# nixie_board.net
KiCad netlist of a schematic drawn in EAGLE
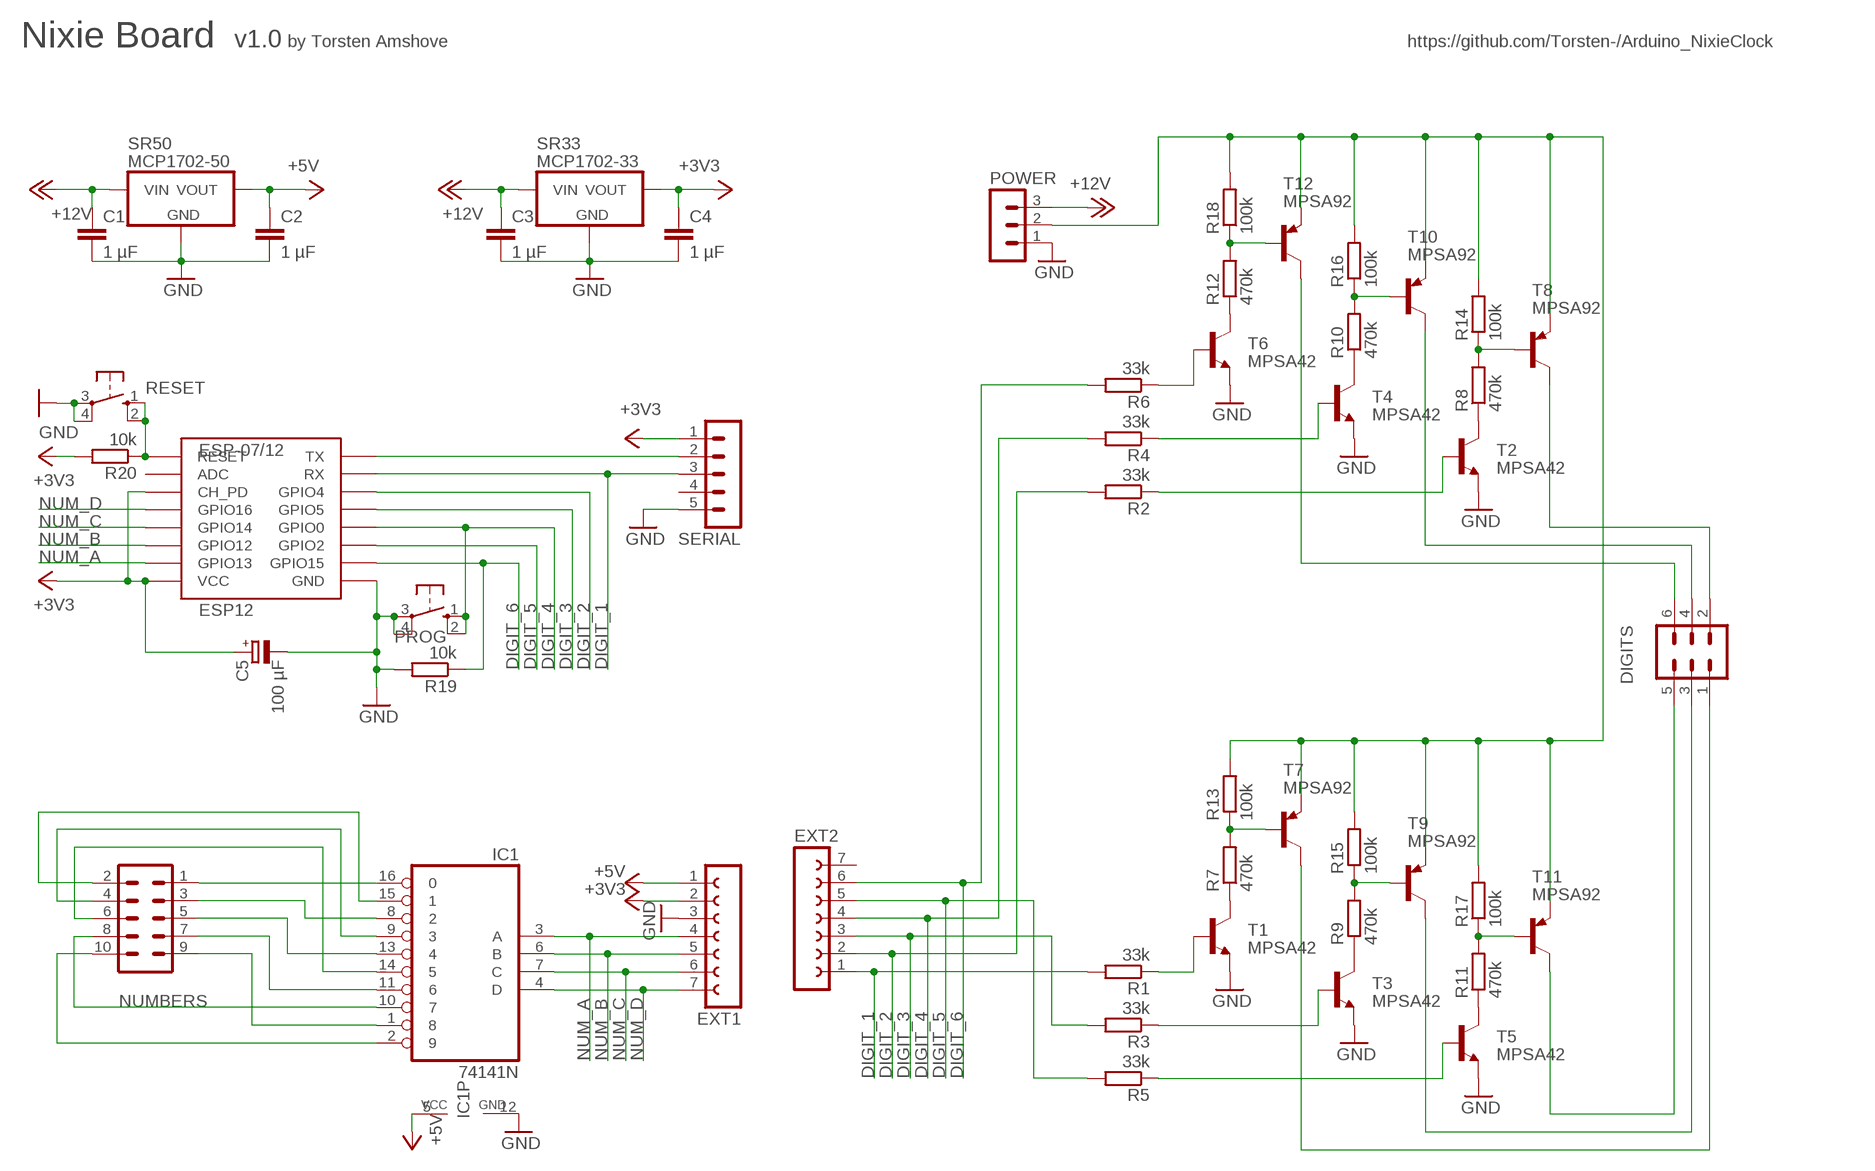
[diagram p0: schematic, sheet 1]

(export (version "E")
  (design (tool "Eeschema 10.0.6"))
  (components
    (comp (ref "C1")
      (value "1 µF")
      (footprint "eagle-import:C5B4.5")
      (libsource (lib "eagle-import") (part "C5/4.5"))
    )
    (comp (ref "C2")
      (value "1 µF")
      (footprint "eagle-import:C5B4.5")
      (libsource (lib "eagle-import") (part "C5/4.5"))
    )
    (comp (ref "C3")
      (value "1 µF")
      (footprint "eagle-import:C5B4.5")
      (libsource (lib "eagle-import") (part "C5/4.5"))
    )
    (comp (ref "C4")
      (value "1 µF")
      (footprint "eagle-import:C5B4.5")
      (libsource (lib "eagle-import") (part "C5/4.5"))
    )
    (comp (ref "C5")
      (value "100 µF")
      (footprint "eagle-import:E2,5-6")
      (libsource (lib "eagle-import") (part "CPOL-EUE2.5-6"))
    )
    (comp (ref "DIGITS")
      (value "MA03-2")
      (footprint "eagle-import:MA03-2")
      (libsource (lib "eagle-import") (part "MA03-2"))
    )
    (comp (ref "ESP-07/12")
      (value "ESP12")
      (footprint "eagle-import:ESP12")
      (libsource (lib "eagle-import") (part "ESP12"))
    )
    (comp (ref "EXT1")
      (value "FE07-1")
      (footprint "eagle-import:FE07")
      (libsource (lib "eagle-import") (part "FE07-1"))
    )
    (comp (ref "EXT2")
      (value "FE07-1")
      (footprint "eagle-import:FE07")
      (libsource (lib "eagle-import") (part "FE07-1"))
    )
    (comp (ref "IC1")
      (value "74141N")
      (footprint "eagle-import:DIL16")
      (libsource (lib "eagle-import") (part "74141N"))
    )
    (comp (ref "NUMBERS")
      (value "MA05-2")
      (footprint "eagle-import:MA05-2")
      (libsource (lib "eagle-import") (part "MA05-2"))
    )
    (comp (ref "POWER")
      (value "MA03-1")
      (footprint "eagle-import:MA03-1")
      (libsource (lib "eagle-import") (part "MA03-1"))
    )
    (comp (ref "PROG")
      (value "10-XX")
      (footprint "eagle-import:B3F-10XX")
      (fields (field (name "MPN") "B3F-1000"))
      (libsource (lib "eagle-import") (part "10-XX"))
    )
    (comp (ref "R1")
      (value "33k")
      (footprint "eagle-import:0204_7")
      (libsource (lib "eagle-import") (part "R-EU_0204/7"))
    )
    (comp (ref "R2")
      (value "33k")
      (footprint "eagle-import:0204_7")
      (libsource (lib "eagle-import") (part "R-EU_0204/7"))
    )
    (comp (ref "R3")
      (value "33k")
      (footprint "eagle-import:0204_7")
      (libsource (lib "eagle-import") (part "R-EU_0204/7"))
    )
    (comp (ref "R4")
      (value "33k")
      (footprint "eagle-import:0204_7")
      (libsource (lib "eagle-import") (part "R-EU_0204/7"))
    )
    (comp (ref "R5")
      (value "33k")
      (footprint "eagle-import:0204_7")
      (libsource (lib "eagle-import") (part "R-EU_0204/7"))
    )
    (comp (ref "R6")
      (value "33k")
      (footprint "eagle-import:0204_7")
      (libsource (lib "eagle-import") (part "R-EU_0204/7"))
    )
    (comp (ref "R7")
      (value "470k")
      (footprint "eagle-import:0204_7")
      (libsource (lib "eagle-import") (part "R-EU_0204/7"))
    )
    (comp (ref "R8")
      (value "470k")
      (footprint "eagle-import:0204_7")
      (libsource (lib "eagle-import") (part "R-EU_0204/7"))
    )
    (comp (ref "R9")
      (value "470k")
      (footprint "eagle-import:0204_7")
      (libsource (lib "eagle-import") (part "R-EU_0204/7"))
    )
    (comp (ref "R10")
      (value "470k")
      (footprint "eagle-import:0204_7")
      (libsource (lib "eagle-import") (part "R-EU_0204/7"))
    )
    (comp (ref "R11")
      (value "470k")
      (footprint "eagle-import:0204_7")
      (libsource (lib "eagle-import") (part "R-EU_0204/7"))
    )
    (comp (ref "R12")
      (value "470k")
      (footprint "eagle-import:0204_7")
      (libsource (lib "eagle-import") (part "R-EU_0204/7"))
    )
    (comp (ref "R13")
      (value "100k")
      (footprint "eagle-import:0207_2V")
      (libsource (lib "eagle-import") (part "R-EU_0207/2V"))
    )
    (comp (ref "R14")
      (value "100k")
      (footprint "eagle-import:0207_2V")
      (libsource (lib "eagle-import") (part "R-EU_0207/2V"))
    )
    (comp (ref "R15")
      (value "100k")
      (footprint "eagle-import:0207_2V")
      (libsource (lib "eagle-import") (part "R-EU_0207/2V"))
    )
    (comp (ref "R16")
      (value "100k")
      (footprint "eagle-import:0207_2V")
      (libsource (lib "eagle-import") (part "R-EU_0207/2V"))
    )
    (comp (ref "R17")
      (value "100k")
      (footprint "eagle-import:0207_2V")
      (libsource (lib "eagle-import") (part "R-EU_0207/2V"))
    )
    (comp (ref "R18")
      (value "100k")
      (footprint "eagle-import:0207_2V")
      (libsource (lib "eagle-import") (part "R-EU_0207/2V"))
    )
    (comp (ref "R19")
      (value "10k")
      (footprint "eagle-import:0204_7")
      (libsource (lib "eagle-import") (part "R-EU_0204/7"))
    )
    (comp (ref "R20")
      (value "10k")
      (footprint "eagle-import:0204_7")
      (libsource (lib "eagle-import") (part "R-EU_0204/7"))
    )
    (comp (ref "RESET")
      (value "10-XX")
      (footprint "eagle-import:B3F-10XX")
      (fields (field (name "MPN") "B3F-1000"))
      (libsource (lib "eagle-import") (part "10-XX"))
    )
    (comp (ref "SERIAL")
      (value "MA05-1")
      (footprint "eagle-import:MA05-1")
      (libsource (lib "eagle-import") (part "MA05-1"))
    )
    (comp (ref "SR33")
      (value "MCP1702-33")
      (footprint "eagle-import:TO-92")
      (libsource (lib "eagle-import") (part "MCP1702"))
    )
    (comp (ref "SR50")
      (value "MCP1702-50")
      (footprint "eagle-import:TO-92")
      (libsource (lib "eagle-import") (part "MCP1702"))
    )
    (comp (ref "T1")
      (value "MPSA42")
      (footprint "eagle-import:TO92-EBC")
      (libsource (lib "eagle-import") (part "-NPN-TO92-EBCMPSA42"))
    )
    (comp (ref "T2")
      (value "MPSA42")
      (footprint "eagle-import:TO92-EBC")
      (libsource (lib "eagle-import") (part "-NPN-TO92-EBCMPSA42"))
    )
    (comp (ref "T3")
      (value "MPSA42")
      (footprint "eagle-import:TO92-EBC")
      (libsource (lib "eagle-import") (part "-NPN-TO92-EBCMPSA42"))
    )
    (comp (ref "T4")
      (value "MPSA42")
      (footprint "eagle-import:TO92-EBC")
      (libsource (lib "eagle-import") (part "-NPN-TO92-EBCMPSA42"))
    )
    (comp (ref "T5")
      (value "MPSA42")
      (footprint "eagle-import:TO92-EBC")
      (libsource (lib "eagle-import") (part "-NPN-TO92-EBCMPSA42"))
    )
    (comp (ref "T6")
      (value "MPSA42")
      (footprint "eagle-import:TO92-EBC")
      (libsource (lib "eagle-import") (part "-NPN-TO92-EBCMPSA42"))
    )
    (comp (ref "T7")
      (value "MPSA92")
      (footprint "eagle-import:TO92-EBC")
      (libsource (lib "eagle-import") (part "-PNP-TO92-EBCMPSA92"))
    )
    (comp (ref "T8")
      (value "MPSA92")
      (footprint "eagle-import:TO92-EBC")
      (libsource (lib "eagle-import") (part "-PNP-TO92-EBCMPSA92"))
    )
    (comp (ref "T9")
      (value "MPSA92")
      (footprint "eagle-import:TO92-EBC")
      (libsource (lib "eagle-import") (part "-PNP-TO92-EBCMPSA92"))
    )
    (comp (ref "T10")
      (value "MPSA92")
      (footprint "eagle-import:TO92-EBC")
      (libsource (lib "eagle-import") (part "-PNP-TO92-EBCMPSA92"))
    )
    (comp (ref "T11")
      (value "MPSA92")
      (footprint "eagle-import:TO92-EBC")
      (libsource (lib "eagle-import") (part "-PNP-TO92-EBCMPSA92"))
    )
    (comp (ref "T12")
      (value "MPSA92")
      (footprint "eagle-import:TO92-EBC")
      (libsource (lib "eagle-import") (part "-PNP-TO92-EBCMPSA92"))
    )
  )
  (nets
    (net (code "1") (name "+3V3") (class "Default")
      (node (ref "C4") (pin "1") (pinfunction "1_1") (pintype "passive"))
      (node (ref "C5") (pin "+") (pinfunction "+_+") (pintype "passive"))
      (node (ref "ESP-07/12") (pin "CH_PD") (pinfunction "CH_PD_CH_PD") (pintype "bidirectional"))
      (node (ref "ESP-07/12") (pin "VCC") (pinfunction "VCC_VCC") (pintype "bidirectional"))
      (node (ref "EXT1") (pin "2") (pinfunction "2_2") (pintype "passive"))
      (node (ref "R20") (pin "2") (pinfunction "2_2") (pintype "passive"))
      (node (ref "SERIAL") (pin "1") (pinfunction "1_1") (pintype "passive"))
      (node (ref "SR33") (pin "3") (pinfunction "VOUT_3") (pintype "passive"))
    )
    (net (code "2") (name "+5V") (class "Default")
      (node (ref "C2") (pin "1") (pinfunction "1_1") (pintype "passive"))
      (node (ref "EXT1") (pin "1") (pinfunction "1_1") (pintype "passive"))
      (node (ref "IC1") (pin "5") (pinfunction "VCC_5") (pintype "power_in"))
      (node (ref "SR50") (pin "3") (pinfunction "VOUT_3") (pintype "passive"))
    )
    (net (code "3") (name "+12V") (class "Default")
      (node (ref "C1") (pin "1") (pinfunction "1_1") (pintype "passive"))
      (node (ref "C3") (pin "1") (pinfunction "1_1") (pintype "passive"))
      (node (ref "POWER") (pin "3") (pinfunction "3_3") (pintype "passive"))
      (node (ref "SR33") (pin "2") (pinfunction "VIN_2") (pintype "input"))
      (node (ref "SR50") (pin "2") (pinfunction "VIN_2") (pintype "input"))
    )
    (net (code "4") (name "/DIGIT_1") (class "Default")
      (node (ref "ESP-07/12") (pin "RX") (pinfunction "RX_RX") (pintype "bidirectional"))
      (node (ref "EXT2") (pin "1") (pinfunction "1_1") (pintype "passive"))
      (node (ref "R1") (pin "2") (pinfunction "2_2") (pintype "passive"))
      (node (ref "SERIAL") (pin "3") (pinfunction "3_3") (pintype "passive"))
    )
    (net (code "5") (name "/DIGIT_2") (class "Default")
      (node (ref "ESP-07/12") (pin "GPIO4") (pinfunction "GPIO4_GPIO4") (pintype "bidirectional"))
      (node (ref "EXT2") (pin "2") (pinfunction "2_2") (pintype "passive"))
      (node (ref "R2") (pin "2") (pinfunction "2_2") (pintype "passive"))
    )
    (net (code "6") (name "/DIGIT_3") (class "Default")
      (node (ref "ESP-07/12") (pin "GPIO5") (pinfunction "GPIO5_GPIO5") (pintype "bidirectional"))
      (node (ref "EXT2") (pin "3") (pinfunction "3_3") (pintype "passive"))
      (node (ref "R3") (pin "2") (pinfunction "2_2") (pintype "passive"))
    )
    (net (code "7") (name "/DIGIT_4") (class "Default")
      (node (ref "ESP-07/12") (pin "GPIO0") (pinfunction "GPIO0_GPIO0") (pintype "bidirectional"))
      (node (ref "EXT2") (pin "4") (pinfunction "4_4") (pintype "passive"))
      (node (ref "PROG") (pin "1") (pinfunction "S_1") (pintype "passive"))
      (node (ref "PROG") (pin "2") (pinfunction "S1_2") (pintype "passive"))
      (node (ref "R4") (pin "2") (pinfunction "2_2") (pintype "passive"))
    )
    (net (code "8") (name "/DIGIT_5") (class "Default")
      (node (ref "ESP-07/12") (pin "GPIO2") (pinfunction "GPIO2_GPIO2") (pintype "bidirectional"))
      (node (ref "EXT2") (pin "5") (pinfunction "5_5") (pintype "passive"))
      (node (ref "R5") (pin "2") (pinfunction "2_2") (pintype "passive"))
    )
    (net (code "9") (name "/DIGIT_6") (class "Default")
      (node (ref "ESP-07/12") (pin "GPIO15") (pinfunction "GPIO15_GPIO15") (pintype "bidirectional"))
      (node (ref "EXT2") (pin "6") (pinfunction "6_6") (pintype "passive"))
      (node (ref "R19") (pin "1") (pinfunction "1_1") (pintype "passive"))
      (node (ref "R6") (pin "2") (pinfunction "2_2") (pintype "passive"))
    )
    (net (code "10") (name "/NUM_A") (class "Default")
      (node (ref "ESP-07/12") (pin "GPIO13") (pinfunction "GPIO13_GPIO13") (pintype "bidirectional"))
      (node (ref "EXT1") (pin "4") (pinfunction "4_4") (pintype "passive"))
      (node (ref "IC1") (pin "3") (pinfunction "A_3") (pintype "input"))
    )
    (net (code "11") (name "/NUM_B") (class "Default")
      (node (ref "ESP-07/12") (pin "GPIO12") (pinfunction "GPIO12_GPIO12") (pintype "bidirectional"))
      (node (ref "EXT1") (pin "5") (pinfunction "5_5") (pintype "passive"))
      (node (ref "IC1") (pin "6") (pinfunction "B_6") (pintype "input"))
    )
    (net (code "12") (name "/NUM_C") (class "Default")
      (node (ref "ESP-07/12") (pin "GPIO14") (pinfunction "GPIO14_GPIO14") (pintype "bidirectional"))
      (node (ref "EXT1") (pin "6") (pinfunction "6_6") (pintype "passive"))
      (node (ref "IC1") (pin "7") (pinfunction "C_7") (pintype "input"))
    )
    (net (code "13") (name "/NUM_D") (class "Default")
      (node (ref "ESP-07/12") (pin "GPIO16") (pinfunction "GPIO16_GPIO16") (pintype "bidirectional"))
      (node (ref "EXT1") (pin "7") (pinfunction "7_7") (pintype "passive"))
      (node (ref "IC1") (pin "4") (pinfunction "D_4") (pintype "input"))
    )
    (net (code "14") (name "GND") (class "Default")
      (node (ref "C1") (pin "2") (pinfunction "2_2") (pintype "passive"))
      (node (ref "C2") (pin "2") (pinfunction "2_2") (pintype "passive"))
      (node (ref "C3") (pin "2") (pinfunction "2_2") (pintype "passive"))
      (node (ref "C4") (pin "2") (pinfunction "2_2") (pintype "passive"))
      (node (ref "C5") (pin "-") (pinfunction "-_-") (pintype "passive"))
      (node (ref "ESP-07/12") (pin "GND") (pinfunction "GND_GND") (pintype "bidirectional"))
      (node (ref "EXT1") (pin "3") (pinfunction "3_3") (pintype "passive"))
      (node (ref "IC1") (pin "12") (pinfunction "GND_12") (pintype "power_in"))
      (node (ref "POWER") (pin "1") (pinfunction "1_1") (pintype "passive"))
      (node (ref "PROG") (pin "3") (pinfunction "P_3") (pintype "passive"))
      (node (ref "PROG") (pin "4") (pinfunction "P1_4") (pintype "passive"))
      (node (ref "R19") (pin "2") (pinfunction "2_2") (pintype "passive"))
      (node (ref "RESET") (pin "3") (pinfunction "P_3") (pintype "passive"))
      (node (ref "RESET") (pin "4") (pinfunction "P1_4") (pintype "passive"))
      (node (ref "SERIAL") (pin "5") (pinfunction "5_5") (pintype "passive"))
      (node (ref "SR33") (pin "1") (pinfunction "GND_1") (pintype "passive"))
      (node (ref "SR50") (pin "1") (pinfunction "GND_1") (pintype "passive"))
      (node (ref "T1") (pin "E") (pinfunction "E_E") (pintype "passive"))
      (node (ref "T2") (pin "E") (pinfunction "E_E") (pintype "passive"))
      (node (ref "T3") (pin "E") (pinfunction "E_E") (pintype "passive"))
      (node (ref "T4") (pin "E") (pinfunction "E_E") (pintype "passive"))
      (node (ref "T5") (pin "E") (pinfunction "E_E") (pintype "passive"))
      (node (ref "T6") (pin "E") (pinfunction "E_E") (pintype "passive"))
    )
    (net (code "15") (name "Net-(DIGITS-Pad1)") (class "Default")
      (node (ref "DIGITS") (pin "1") (pinfunction "1_1") (pintype "passive"))
      (node (ref "T7") (pin "C") (pinfunction "C_C") (pintype "passive"))
    )
    (net (code "16") (name "Net-(DIGITS-Pad2)") (class "Default")
      (node (ref "DIGITS") (pin "2") (pinfunction "2_2") (pintype "passive"))
      (node (ref "T8") (pin "C") (pinfunction "C_C") (pintype "passive"))
    )
    (net (code "17") (name "Net-(DIGITS-Pad3)") (class "Default")
      (node (ref "DIGITS") (pin "3") (pinfunction "3_3") (pintype "passive"))
      (node (ref "T9") (pin "C") (pinfunction "C_C") (pintype "passive"))
    )
    (net (code "18") (name "Net-(DIGITS-Pad4)") (class "Default")
      (node (ref "DIGITS") (pin "4") (pinfunction "4_4") (pintype "passive"))
      (node (ref "T10") (pin "C") (pinfunction "C_C") (pintype "passive"))
    )
    (net (code "19") (name "Net-(DIGITS-Pad5)") (class "Default")
      (node (ref "DIGITS") (pin "5") (pinfunction "5_5") (pintype "passive"))
      (node (ref "T11") (pin "C") (pinfunction "C_C") (pintype "passive"))
    )
    (net (code "20") (name "Net-(DIGITS-Pad6)") (class "Default")
      (node (ref "DIGITS") (pin "6") (pinfunction "6_6") (pintype "passive"))
      (node (ref "T12") (pin "C") (pinfunction "C_C") (pintype "passive"))
    )
    (net (code "21") (name "Net-(ESP-07/12-PadTX)") (class "Default")
      (node (ref "ESP-07/12") (pin "TX") (pinfunction "TX_TX") (pintype "bidirectional"))
      (node (ref "SERIAL") (pin "2") (pinfunction "2_2") (pintype "passive"))
    )
    (net (code "22") (name "Net-(IC1A-0)") (class "Default")
      (node (ref "IC1") (pin "16") (pinfunction "0_16") (pintype "open_collector"))
      (node (ref "NUMBERS") (pin "1") (pinfunction "1_1") (pintype "passive"))
    )
    (net (code "23") (name "Net-(IC1A-1)") (class "Default")
      (node (ref "IC1") (pin "15") (pinfunction "1_15") (pintype "open_collector"))
      (node (ref "NUMBERS") (pin "2") (pinfunction "2_2") (pintype "passive"))
    )
    (net (code "24") (name "Net-(IC1A-2)") (class "Default")
      (node (ref "IC1") (pin "8") (pinfunction "2_8") (pintype "open_collector"))
      (node (ref "NUMBERS") (pin "3") (pinfunction "3_3") (pintype "passive"))
    )
    (net (code "25") (name "Net-(IC1A-3)") (class "Default")
      (node (ref "IC1") (pin "9") (pinfunction "3_9") (pintype "open_collector"))
      (node (ref "NUMBERS") (pin "4") (pinfunction "4_4") (pintype "passive"))
    )
    (net (code "26") (name "Net-(IC1A-4)") (class "Default")
      (node (ref "IC1") (pin "13") (pinfunction "4_13") (pintype "open_collector"))
      (node (ref "NUMBERS") (pin "5") (pinfunction "5_5") (pintype "passive"))
    )
    (net (code "27") (name "Net-(IC1A-5)") (class "Default")
      (node (ref "IC1") (pin "14") (pinfunction "5_14") (pintype "open_collector"))
      (node (ref "NUMBERS") (pin "6") (pinfunction "6_6") (pintype "passive"))
    )
    (net (code "28") (name "Net-(IC1A-6)") (class "Default")
      (node (ref "IC1") (pin "11") (pinfunction "6_11") (pintype "open_collector"))
      (node (ref "NUMBERS") (pin "7") (pinfunction "7_7") (pintype "passive"))
    )
    (net (code "29") (name "Net-(IC1A-7)") (class "Default")
      (node (ref "IC1") (pin "10") (pinfunction "7_10") (pintype "open_collector"))
      (node (ref "NUMBERS") (pin "8") (pinfunction "8_8") (pintype "passive"))
    )
    (net (code "30") (name "Net-(IC1A-8)") (class "Default")
      (node (ref "IC1") (pin "1") (pinfunction "8_1") (pintype "open_collector"))
      (node (ref "NUMBERS") (pin "9") (pinfunction "9_9") (pintype "passive"))
    )
    (net (code "31") (name "Net-(IC1A-9)") (class "Default")
      (node (ref "IC1") (pin "2") (pinfunction "9_2") (pintype "open_collector"))
      (node (ref "NUMBERS") (pin "10") (pinfunction "10_10") (pintype "passive"))
    )
    (net (code "32") (name "Net-(POWER-Pad2)") (class "Default")
      (node (ref "POWER") (pin "2") (pinfunction "2_2") (pintype "passive"))
      (node (ref "R13") (pin "2") (pinfunction "2_2") (pintype "passive"))
      (node (ref "R14") (pin "2") (pinfunction "2_2") (pintype "passive"))
      (node (ref "R15") (pin "2") (pinfunction "2_2") (pintype "passive"))
      (node (ref "R16") (pin "2") (pinfunction "2_2") (pintype "passive"))
      (node (ref "R17") (pin "2") (pinfunction "2_2") (pintype "passive"))
      (node (ref "R18") (pin "2") (pinfunction "2_2") (pintype "passive"))
      (node (ref "T10") (pin "E") (pinfunction "E_E") (pintype "passive"))
      (node (ref "T11") (pin "E") (pinfunction "E_E") (pintype "passive"))
      (node (ref "T12") (pin "E") (pinfunction "E_E") (pintype "passive"))
      (node (ref "T7") (pin "E") (pinfunction "E_E") (pintype "passive"))
      (node (ref "T8") (pin "E") (pinfunction "E_E") (pintype "passive"))
      (node (ref "T9") (pin "E") (pinfunction "E_E") (pintype "passive"))
    )
    (net (code "33") (name "Net-(R1-Pad1)") (class "Default")
      (node (ref "R1") (pin "1") (pinfunction "1_1") (pintype "passive"))
      (node (ref "T1") (pin "B") (pinfunction "B_B") (pintype "passive"))
    )
    (net (code "34") (name "Net-(R2-Pad1)") (class "Default")
      (node (ref "R2") (pin "1") (pinfunction "1_1") (pintype "passive"))
      (node (ref "T2") (pin "B") (pinfunction "B_B") (pintype "passive"))
    )
    (net (code "35") (name "Net-(R3-Pad1)") (class "Default")
      (node (ref "R3") (pin "1") (pinfunction "1_1") (pintype "passive"))
      (node (ref "T3") (pin "B") (pinfunction "B_B") (pintype "passive"))
    )
    (net (code "36") (name "Net-(R4-Pad1)") (class "Default")
      (node (ref "R4") (pin "1") (pinfunction "1_1") (pintype "passive"))
      (node (ref "T4") (pin "B") (pinfunction "B_B") (pintype "passive"))
    )
    (net (code "37") (name "Net-(R5-Pad1)") (class "Default")
      (node (ref "R5") (pin "1") (pinfunction "1_1") (pintype "passive"))
      (node (ref "T5") (pin "B") (pinfunction "B_B") (pintype "passive"))
    )
    (net (code "38") (name "Net-(R6-Pad1)") (class "Default")
      (node (ref "R6") (pin "1") (pinfunction "1_1") (pintype "passive"))
      (node (ref "T6") (pin "B") (pinfunction "B_B") (pintype "passive"))
    )
    (net (code "39") (name "Net-(R7-Pad1)") (class "Default")
      (node (ref "R7") (pin "1") (pinfunction "1_1") (pintype "passive"))
      (node (ref "T1") (pin "C") (pinfunction "C_C") (pintype "passive"))
    )
    (net (code "40") (name "Net-(R8-Pad1)") (class "Default")
      (node (ref "R8") (pin "1") (pinfunction "1_1") (pintype "passive"))
      (node (ref "T2") (pin "C") (pinfunction "C_C") (pintype "passive"))
    )
    (net (code "41") (name "Net-(R9-Pad1)") (class "Default")
      (node (ref "R9") (pin "1") (pinfunction "1_1") (pintype "passive"))
      (node (ref "T3") (pin "C") (pinfunction "C_C") (pintype "passive"))
    )
    (net (code "42") (name "Net-(R10-Pad1)") (class "Default")
      (node (ref "R10") (pin "1") (pinfunction "1_1") (pintype "passive"))
      (node (ref "T4") (pin "C") (pinfunction "C_C") (pintype "passive"))
    )
    (net (code "43") (name "Net-(R10-Pad2)") (class "Default")
      (node (ref "R10") (pin "2") (pinfunction "2_2") (pintype "passive"))
      (node (ref "R16") (pin "1") (pinfunction "1_1") (pintype "passive"))
      (node (ref "T10") (pin "B") (pinfunction "B_B") (pintype "passive"))
    )
    (net (code "44") (name "Net-(R11-Pad1)") (class "Default")
      (node (ref "R11") (pin "1") (pinfunction "1_1") (pintype "passive"))
      (node (ref "T5") (pin "C") (pinfunction "C_C") (pintype "passive"))
    )
    (net (code "45") (name "Net-(R11-Pad2)") (class "Default")
      (node (ref "R11") (pin "2") (pinfunction "2_2") (pintype "passive"))
      (node (ref "R17") (pin "1") (pinfunction "1_1") (pintype "passive"))
      (node (ref "T11") (pin "B") (pinfunction "B_B") (pintype "passive"))
    )
    (net (code "46") (name "Net-(R12-Pad1)") (class "Default")
      (node (ref "R12") (pin "1") (pinfunction "1_1") (pintype "passive"))
      (node (ref "T6") (pin "C") (pinfunction "C_C") (pintype "passive"))
    )
    (net (code "47") (name "Net-(R12-Pad2)") (class "Default")
      (node (ref "R12") (pin "2") (pinfunction "2_2") (pintype "passive"))
      (node (ref "R18") (pin "1") (pinfunction "1_1") (pintype "passive"))
      (node (ref "T12") (pin "B") (pinfunction "B_B") (pintype "passive"))
    )
    (net (code "48") (name "Net-(R13-Pad1)") (class "Default")
      (node (ref "R13") (pin "1") (pinfunction "1_1") (pintype "passive"))
      (node (ref "R7") (pin "2") (pinfunction "2_2") (pintype "passive"))
      (node (ref "T7") (pin "B") (pinfunction "B_B") (pintype "passive"))
    )
    (net (code "49") (name "Net-(R14-Pad1)") (class "Default")
      (node (ref "R14") (pin "1") (pinfunction "1_1") (pintype "passive"))
      (node (ref "R8") (pin "2") (pinfunction "2_2") (pintype "passive"))
      (node (ref "T8") (pin "B") (pinfunction "B_B") (pintype "passive"))
    )
    (net (code "50") (name "Net-(R15-Pad1)") (class "Default")
      (node (ref "R15") (pin "1") (pinfunction "1_1") (pintype "passive"))
      (node (ref "R9") (pin "2") (pinfunction "2_2") (pintype "passive"))
      (node (ref "T9") (pin "B") (pinfunction "B_B") (pintype "passive"))
    )
    (net (code "51") (name "Net-(RESET-S)") (class "Default")
      (node (ref "ESP-07/12") (pin "RESET") (pinfunction "RESET_RESET") (pintype "bidirectional"))
      (node (ref "R20") (pin "1") (pinfunction "1_1") (pintype "passive"))
      (node (ref "RESET") (pin "1") (pinfunction "S_1") (pintype "passive"))
      (node (ref "RESET") (pin "2") (pinfunction "S1_2") (pintype "passive"))
    )
    (net (code "52") (name "unconnected-(ESP-07/12-PadADC)") (class "Default")
      (node (ref "ESP-07/12") (pin "ADC") (pinfunction "ADC_ADC") (pintype "bidirectional"))
    )
    (net (code "53") (name "unconnected-(EXT2-Pad7)") (class "Default")
      (node (ref "EXT2") (pin "7") (pinfunction "7_7") (pintype "passive"))
    )
    (net (code "54") (name "unconnected-(SERIAL-Pad4)") (class "Default")
      (node (ref "SERIAL") (pin "4") (pinfunction "4_4") (pintype "passive"))
    )
  )
)
